# CustComp_1_1.net
KiCad netlist of a schematic drawn in EAGLE
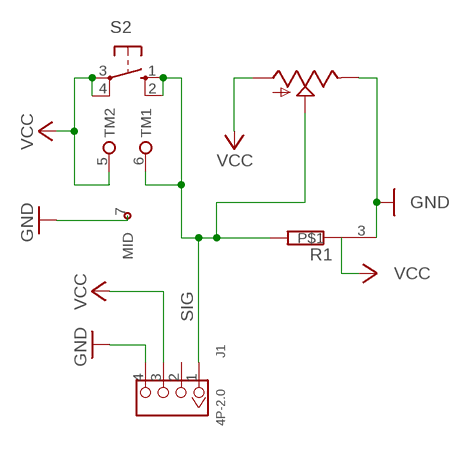
[diagram p0: schematic, sheet 1]

(export (version "E")
  (design (tool "Eeschema 10.0.6"))
  (components
    (comp (ref "J1")
      (value "4P-2.0")
      (footprint "eagle-import:HW4-2.0")
      (libsource (lib "eagle-import") (part "GROVE-CONNECTOR-DIP(4P-2.0)"))
    )
    (comp (ref "R1")
      (value "RES_PULL_UP_DOWNRES_PULL_UP_DOWN_ANGLE")
      (footprint "eagle-import:RES_PULL_UP_DOWN_ANGLE")
      (libsource (lib "eagle-import") (part "RES_PULL_UP_DOWNRES_PULL_UP_DOWN_ANGLE"))
    )
    (comp (ref "S2")
      (value "TERMINAL_TAC_SWITCHTERMINAL3.81_TAC12-PTH")
      (footprint "eagle-import:TERMINAL3.81_TAC12-PTH")
      (libsource (lib "eagle-import") (part "TERMINAL_TAC_SWITCHTERMINAL3.81_TAC12-PTH"))
    )
    (comp (ref "U$1")
      (value "SPARKFUN_POT")
      (footprint "eagle-import:SPARKFUN_ALPS_POT")
      (libsource (lib "eagle-import") (part "SPARKFUN_POT"))
    )
  )
  (nets
    (net (code "1") (name "/SIG") (class "Default")
      (node (ref "J1") (pin "1") (pinfunction "1_1") (pintype "bidirectional"))
      (node (ref "R1") (pin "1") (pinfunction "2_1") (pintype "passive"))
      (node (ref "S2") (pin "1") (pinfunction "3_1") (pintype "passive"))
      (node (ref "S2") (pin "2") (pinfunction "4_2") (pintype "passive"))
      (node (ref "S2") (pin "6") (pinfunction "TM1_6") (pintype "bidirectional"))
      (node (ref "U$1") (pin "P$2") (pinfunction "S_P$2") (pintype "passive"))
    )
    (net (code "2") (name "GND") (class "Default")
      (node (ref "J1") (pin "4") (pinfunction "4_4") (pintype "bidirectional"))
      (node (ref "R1") (pin "3") (pinfunction "P$1_3") (pintype "bidirectional"))
      (node (ref "S2") (pin "7") (pinfunction "MID_7") (pintype "bidirectional"))
      (node (ref "U$1") (pin "P$1") (pinfunction "E_P$1") (pintype "passive"))
    )
    (net (code "3") (name "VCC") (class "Default")
      (node (ref "J1") (pin "3") (pinfunction "3_3") (pintype "bidirectional"))
      (node (ref "R1") (pin "2") (pinfunction "1_2") (pintype "passive"))
      (node (ref "S2") (pin "3") (pinfunction "1_3") (pintype "passive"))
      (node (ref "S2") (pin "4") (pinfunction "2_4") (pintype "passive"))
      (node (ref "S2") (pin "5") (pinfunction "TM2_5") (pintype "bidirectional"))
      (node (ref "U$1") (pin "P$3") (pinfunction "A_P$3") (pintype "passive"))
    )
    (net (code "4") (name "unconnected-(J1-Pad2)") (class "Default")
      (node (ref "J1") (pin "2") (pinfunction "2_2") (pintype "bidirectional"))
    )
  )
)
